# xr_vco_pots.net
KiCad netlist of a schematic drawn in EAGLE
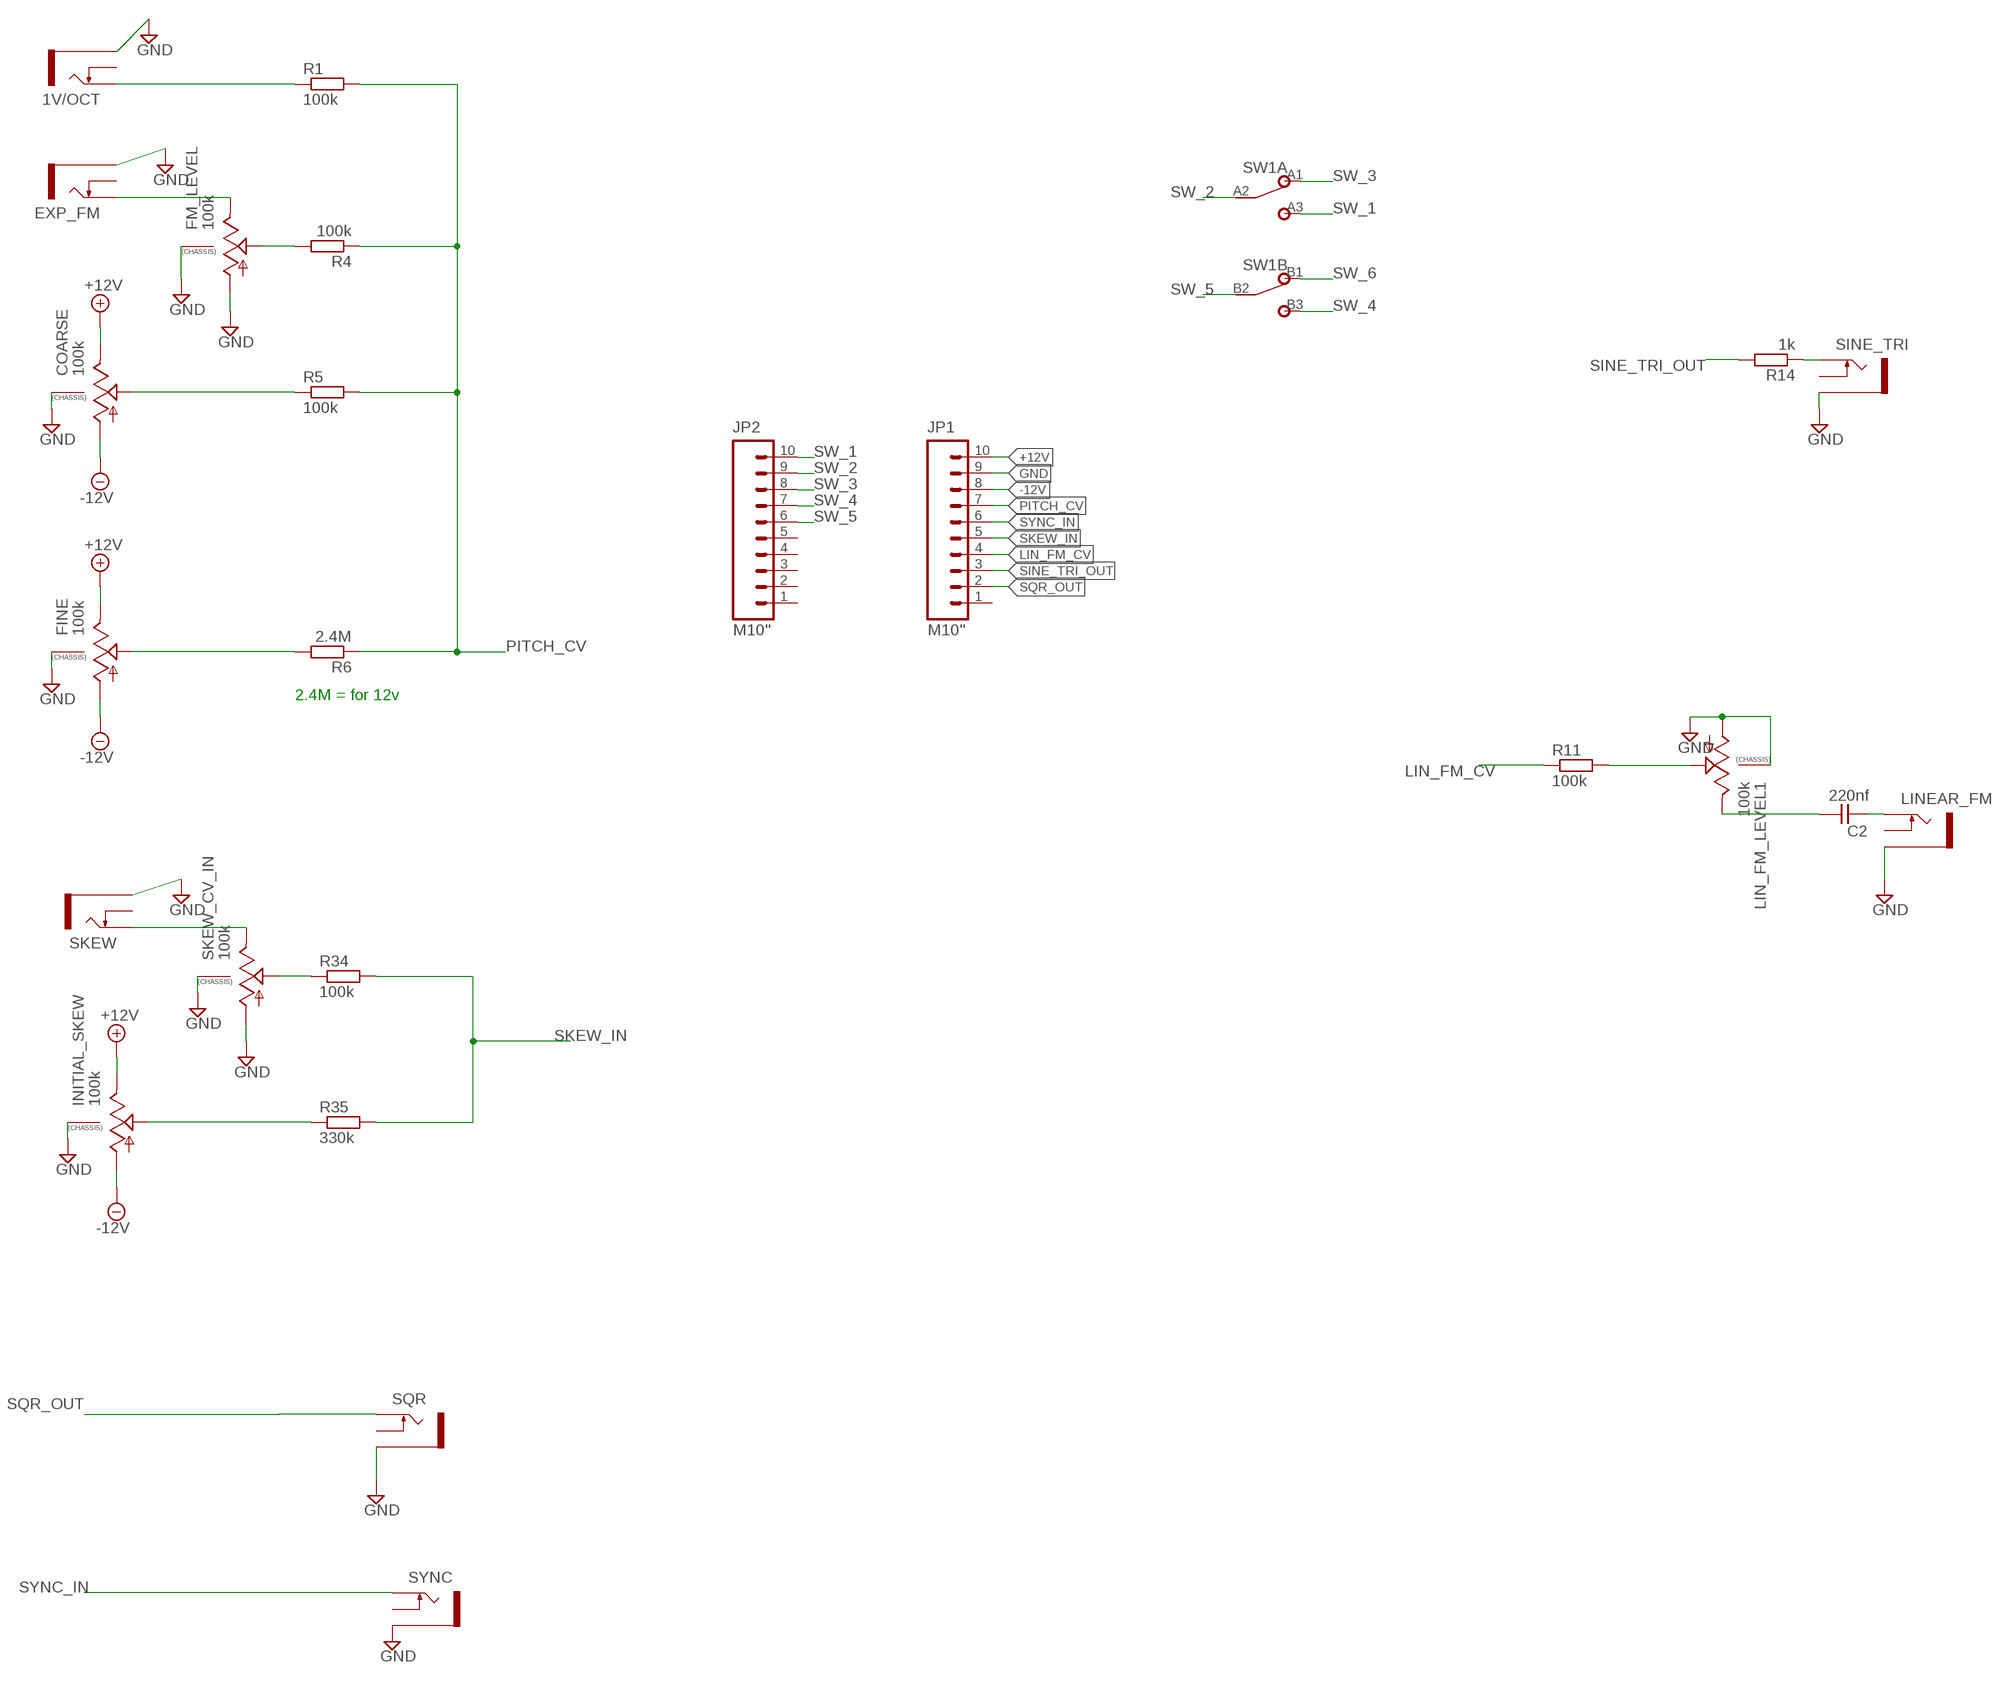
[diagram p0: schematic, sheet 1]

(export (version "E")
  (design (tool "Eeschema 10.0.6"))
  (components
    (comp (ref "1V/OCT")
      (value "THONKICONNNEW")
      (footprint "eagle-import:WQP-PJ301M-12_JACK")
      (libsource (lib "eagle-import") (part "THONKICONNNEW"))
    )
    (comp (ref "C2")
      (value "220nf")
      (footprint "eagle-import:C050-024X044")
      (libsource (lib "eagle-import") (part "C-EU050-024X044"))
    )
    (comp (ref "COARSE")
      (value "100k")
      (footprint "eagle-import:9MM_SNAP-IN_POT")
      (libsource (lib "eagle-import") (part "9MM_SNAP-IN_POT_CHASSIS"))
    )
    (comp (ref "EXP_FM")
      (value "THONKICONNNEW")
      (footprint "eagle-import:WQP-PJ301M-12_JACK")
      (libsource (lib "eagle-import") (part "THONKICONNNEW"))
    )
    (comp (ref "FINE")
      (value "100k")
      (footprint "eagle-import:9MM_SNAP-IN_POT")
      (libsource (lib "eagle-import") (part "9MM_SNAP-IN_POT_CHASSIS"))
    )
    (comp (ref "FM_LEVEL")
      (value "100k")
      (footprint "eagle-import:9MM_SNAP-IN_POT")
      (libsource (lib "eagle-import") (part "9MM_SNAP-IN_POT_CHASSIS"))
    )
    (comp (ref "INITIAL_SKEW")
      (value "100k")
      (footprint "eagle-import:9MM_SNAP-IN_POT")
      (libsource (lib "eagle-import") (part "9MM_SNAP-IN_POT_CHASSIS"))
    )
    (comp (ref "JP1")
      (value "M10\"")
      (footprint "eagle-import:1X10")
      (libsource (lib "eagle-import") (part "M10{dblquote}"))
    )
    (comp (ref "JP2")
      (value "M10\"")
      (footprint "eagle-import:1X10")
      (libsource (lib "eagle-import") (part "M10{dblquote}"))
    )
    (comp (ref "LINEAR_FM")
      (value "THONKICONNNEW")
      (footprint "eagle-import:WQP-PJ301M-12_JACK")
      (libsource (lib "eagle-import") (part "THONKICONNNEW"))
    )
    (comp (ref "LIN_FM_LEVEL1")
      (value "100k")
      (footprint "eagle-import:9MM_SNAP-IN_POT")
      (libsource (lib "eagle-import") (part "9MM_SNAP-IN_POT_CHASSIS"))
    )
    (comp (ref "R1")
      (value "100k")
      (footprint "eagle-import:7MM_RESISTOR")
      (libsource (lib "eagle-import") (part "RESISTOR7MM"))
    )
    (comp (ref "R4")
      (value "100k")
      (footprint "eagle-import:7MM_RESISTOR")
      (libsource (lib "eagle-import") (part "RESISTOR7MM"))
    )
    (comp (ref "R5")
      (value "100k")
      (footprint "eagle-import:7MM_RESISTOR")
      (libsource (lib "eagle-import") (part "RESISTOR7MM"))
    )
    (comp (ref "R6")
      (value "2.4M")
      (footprint "eagle-import:7MM_RESISTOR")
      (libsource (lib "eagle-import") (part "RESISTOR7MM"))
    )
    (comp (ref "R11")
      (value "100k")
      (footprint "eagle-import:7MM_RESISTOR")
      (libsource (lib "eagle-import") (part "RESISTOR7MM"))
    )
    (comp (ref "R14")
      (value "1k")
      (footprint "eagle-import:7MM_RESISTOR")
      (libsource (lib "eagle-import") (part "RESISTOR7MM"))
    )
    (comp (ref "R34")
      (value "100k")
      (footprint "eagle-import:7MM_RESISTOR")
      (libsource (lib "eagle-import") (part "RESISTOR7MM"))
    )
    (comp (ref "R35")
      (value "330k")
      (footprint "eagle-import:7MM_RESISTOR")
      (libsource (lib "eagle-import") (part "RESISTOR7MM"))
    )
    (comp (ref "SINE_TRI")
      (value "THONKICONNNEW")
      (footprint "eagle-import:WQP-PJ301M-12_JACK")
      (libsource (lib "eagle-import") (part "THONKICONNNEW"))
    )
    (comp (ref "SKEW")
      (value "THONKICONNNEW")
      (footprint "eagle-import:WQP-PJ301M-12_JACK")
      (libsource (lib "eagle-import") (part "THONKICONNNEW"))
    )
    (comp (ref "SKEW_CV_IN")
      (value "100k")
      (footprint "eagle-import:9MM_SNAP-IN_POT")
      (libsource (lib "eagle-import") (part "9MM_SNAP-IN_POT_CHASSIS"))
    )
    (comp (ref "SQR")
      (value "THONKICONNNEW")
      (footprint "eagle-import:WQP-PJ301M-12_JACK")
      (libsource (lib "eagle-import") (part "THONKICONNNEW"))
    )
    (comp (ref "SW1")
      (value "DPDT")
      (footprint "eagle-import:DPDT")
      (libsource (lib "eagle-import") (part "DPDT"))
    )
    (comp (ref "SYNC")
      (value "THONKICONNNEW")
      (footprint "eagle-import:WQP-PJ301M-12_JACK")
      (libsource (lib "eagle-import") (part "THONKICONNNEW"))
    )
  )
  (nets
    (net (code "1") (name "+12V") (class "Default")
      (node (ref "COARSE") (pin "3") (pinfunction "E_3") (pintype "passive"))
      (node (ref "FINE") (pin "3") (pinfunction "E_3") (pintype "passive"))
      (node (ref "INITIAL_SKEW") (pin "3") (pinfunction "E_3") (pintype "passive"))
      (node (ref "JP1") (pin "10") (pinfunction "10_10") (pintype "passive"))
    )
    (net (code "2") (name "-12V") (class "Default")
      (node (ref "COARSE") (pin "1") (pinfunction "A_1") (pintype "passive"))
      (node (ref "FINE") (pin "1") (pinfunction "A_1") (pintype "passive"))
      (node (ref "INITIAL_SKEW") (pin "1") (pinfunction "A_1") (pintype "passive"))
      (node (ref "JP1") (pin "8") (pinfunction "8_8") (pintype "passive"))
    )
    (net (code "3") (name "/SW_1") (class "Default")
      (node (ref "JP2") (pin "10") (pinfunction "10_10") (pintype "passive"))
      (node (ref "SW1") (pin "A3") (pinfunction "3_A3") (pintype "passive"))
    )
    (net (code "4") (name "/SW_2") (class "Default")
      (node (ref "JP2") (pin "9") (pinfunction "9_9") (pintype "passive"))
      (node (ref "SW1") (pin "A2") (pinfunction "2_A2") (pintype "passive"))
    )
    (net (code "5") (name "/SW_3") (class "Default")
      (node (ref "JP2") (pin "8") (pinfunction "8_8") (pintype "passive"))
      (node (ref "SW1") (pin "A1") (pinfunction "1_A1") (pintype "passive"))
    )
    (net (code "6") (name "/SW_4") (class "Default")
      (node (ref "JP2") (pin "7") (pinfunction "7_7") (pintype "passive"))
      (node (ref "SW1") (pin "B3") (pinfunction "3_B3") (pintype "passive"))
    )
    (net (code "7") (name "/SW_5") (class "Default")
      (node (ref "JP2") (pin "6") (pinfunction "6_6") (pintype "passive"))
      (node (ref "SW1") (pin "B2") (pinfunction "2_B2") (pintype "passive"))
    )
    (net (code "8") (name "/SW_6") (class "Default")
      (node (ref "SW1") (pin "B1") (pinfunction "1_B1") (pintype "passive"))
    )
    (net (code "9") (name "GND") (class "Default")
      (node (ref "1V/OCT") (pin "P$3_SLEEVE") (pinfunction "SLEEVE_P$3_SLEEVE") (pintype "passive"))
      (node (ref "COARSE") (pin "CHASSIS2") (pinfunction "P$1_CHASSIS2") (pintype "passive"))
      (node (ref "EXP_FM") (pin "P$3_SLEEVE") (pinfunction "SLEEVE_P$3_SLEEVE") (pintype "passive"))
      (node (ref "FINE") (pin "CHASSIS2") (pinfunction "P$1_CHASSIS2") (pintype "passive"))
      (node (ref "FM_LEVEL") (pin "1") (pinfunction "A_1") (pintype "passive"))
      (node (ref "FM_LEVEL") (pin "CHASSIS2") (pinfunction "P$1_CHASSIS2") (pintype "passive"))
      (node (ref "INITIAL_SKEW") (pin "CHASSIS2") (pinfunction "P$1_CHASSIS2") (pintype "passive"))
      (node (ref "JP1") (pin "9") (pinfunction "9_9") (pintype "passive"))
      (node (ref "LINEAR_FM") (pin "P$3_SLEEVE") (pinfunction "SLEEVE_P$3_SLEEVE") (pintype "passive"))
      (node (ref "LIN_FM_LEVEL1") (pin "1") (pinfunction "A_1") (pintype "passive"))
      (node (ref "LIN_FM_LEVEL1") (pin "CHASSIS2") (pinfunction "P$1_CHASSIS2") (pintype "passive"))
      (node (ref "SINE_TRI") (pin "P$3_SLEEVE") (pinfunction "SLEEVE_P$3_SLEEVE") (pintype "passive"))
      (node (ref "SKEW") (pin "P$3_SLEEVE") (pinfunction "SLEEVE_P$3_SLEEVE") (pintype "passive"))
      (node (ref "SKEW_CV_IN") (pin "1") (pinfunction "A_1") (pintype "passive"))
      (node (ref "SKEW_CV_IN") (pin "CHASSIS2") (pinfunction "P$1_CHASSIS2") (pintype "passive"))
      (node (ref "SQR") (pin "P$3_SLEEVE") (pinfunction "SLEEVE_P$3_SLEEVE") (pintype "passive"))
      (node (ref "SYNC") (pin "P$3_SLEEVE") (pinfunction "SLEEVE_P$3_SLEEVE") (pintype "passive"))
    )
    (net (code "10") (name "LIN_FM_CV") (class "Default")
      (node (ref "JP1") (pin "4") (pinfunction "4_4") (pintype "passive"))
      (node (ref "R11") (pin "1") (pinfunction "1_1") (pintype "passive"))
    )
    (net (code "11") (name "Net-(1V/OCT-TIP)") (class "Default")
      (node (ref "1V/OCT") (pin "P$1_TIP") (pinfunction "TIP_P$1_TIP") (pintype "passive"))
      (node (ref "R1") (pin "1") (pinfunction "1_1") (pintype "passive"))
    )
    (net (code "12") (name "Net-(COARSE-S)") (class "Default")
      (node (ref "COARSE") (pin "2") (pinfunction "S_2") (pintype "passive"))
      (node (ref "R5") (pin "1") (pinfunction "1_1") (pintype "passive"))
    )
    (net (code "13") (name "Net-(EXP_FM-TIP)") (class "Default")
      (node (ref "EXP_FM") (pin "P$1_TIP") (pinfunction "TIP_P$1_TIP") (pintype "passive"))
      (node (ref "FM_LEVEL") (pin "3") (pinfunction "E_3") (pintype "passive"))
    )
    (net (code "14") (name "Net-(FINE-S)") (class "Default")
      (node (ref "FINE") (pin "2") (pinfunction "S_2") (pintype "passive"))
      (node (ref "R6") (pin "2") (pinfunction "2_2") (pintype "passive"))
    )
    (net (code "15") (name "Net-(FM_LEVEL-S)") (class "Default")
      (node (ref "FM_LEVEL") (pin "2") (pinfunction "S_2") (pintype "passive"))
      (node (ref "R4") (pin "2") (pinfunction "2_2") (pintype "passive"))
    )
    (net (code "16") (name "Net-(INITIAL_SKEW-S)") (class "Default")
      (node (ref "INITIAL_SKEW") (pin "2") (pinfunction "S_2") (pintype "passive"))
      (node (ref "R35") (pin "1") (pinfunction "1_1") (pintype "passive"))
    )
    (net (code "17") (name "Net-(LINEAR_FM-TIP)") (class "Default")
      (node (ref "C2") (pin "2") (pinfunction "2_2") (pintype "passive"))
      (node (ref "LINEAR_FM") (pin "P$1_TIP") (pinfunction "TIP_P$1_TIP") (pintype "passive"))
    )
    (net (code "18") (name "Net-(LIN_FM_LEVEL1-E)") (class "Default")
      (node (ref "C2") (pin "1") (pinfunction "1_1") (pintype "passive"))
      (node (ref "LIN_FM_LEVEL1") (pin "3") (pinfunction "E_3") (pintype "passive"))
    )
    (net (code "19") (name "Net-(LIN_FM_LEVEL1-S)") (class "Default")
      (node (ref "LIN_FM_LEVEL1") (pin "2") (pinfunction "S_2") (pintype "passive"))
      (node (ref "R11") (pin "2") (pinfunction "2_2") (pintype "passive"))
    )
    (net (code "20") (name "Net-(SINE_TRI-TIP)") (class "Default")
      (node (ref "R14") (pin "1") (pinfunction "1_1") (pintype "passive"))
      (node (ref "SINE_TRI") (pin "P$1_TIP") (pinfunction "TIP_P$1_TIP") (pintype "passive"))
    )
    (net (code "21") (name "Net-(SKEW-TIP)") (class "Default")
      (node (ref "SKEW") (pin "P$1_TIP") (pinfunction "TIP_P$1_TIP") (pintype "passive"))
      (node (ref "SKEW_CV_IN") (pin "3") (pinfunction "E_3") (pintype "passive"))
    )
    (net (code "22") (name "Net-(SKEW_CV_IN-S)") (class "Default")
      (node (ref "R34") (pin "1") (pinfunction "1_1") (pintype "passive"))
      (node (ref "SKEW_CV_IN") (pin "2") (pinfunction "S_2") (pintype "passive"))
    )
    (net (code "23") (name "PITCH_CV") (class "Default")
      (node (ref "JP1") (pin "7") (pinfunction "7_7") (pintype "passive"))
      (node (ref "R1") (pin "2") (pinfunction "2_2") (pintype "passive"))
      (node (ref "R4") (pin "1") (pinfunction "1_1") (pintype "passive"))
      (node (ref "R5") (pin "2") (pinfunction "2_2") (pintype "passive"))
      (node (ref "R6") (pin "1") (pinfunction "1_1") (pintype "passive"))
    )
    (net (code "24") (name "SINE_TRI_OUT") (class "Default")
      (node (ref "JP1") (pin "3") (pinfunction "3_3") (pintype "passive"))
      (node (ref "R14") (pin "2") (pinfunction "2_2") (pintype "passive"))
    )
    (net (code "25") (name "SKEW_IN") (class "Default")
      (node (ref "JP1") (pin "5") (pinfunction "5_5") (pintype "passive"))
      (node (ref "R34") (pin "2") (pinfunction "2_2") (pintype "passive"))
      (node (ref "R35") (pin "2") (pinfunction "2_2") (pintype "passive"))
    )
    (net (code "26") (name "SQR_OUT") (class "Default")
      (node (ref "JP1") (pin "2") (pinfunction "2_2") (pintype "passive"))
      (node (ref "SQR") (pin "P$1_TIP") (pinfunction "TIP_P$1_TIP") (pintype "passive"))
    )
    (net (code "27") (name "SYNC_IN") (class "Default")
      (node (ref "JP1") (pin "6") (pinfunction "6_6") (pintype "passive"))
      (node (ref "SYNC") (pin "P$1_TIP") (pinfunction "TIP_P$1_TIP") (pintype "passive"))
    )
    (net (code "28") (name "unconnected-(1V/OCT-SWITCH-PadP$2_SWITCH)") (class "Default")
      (node (ref "1V/OCT") (pin "P$2_SWITCH") (pinfunction "SWITCH_P$2_SWITCH") (pintype "passive"))
    )
    (net (code "29") (name "unconnected-(EXP_FM-SWITCH-PadP$2_SWITCH)") (class "Default")
      (node (ref "EXP_FM") (pin "P$2_SWITCH") (pinfunction "SWITCH_P$2_SWITCH") (pintype "passive"))
    )
    (net (code "30") (name "unconnected-(JP1-Pad1)") (class "Default")
      (node (ref "JP1") (pin "1") (pinfunction "1_1") (pintype "passive"))
    )
    (net (code "31") (name "unconnected-(JP2-Pad1)") (class "Default")
      (node (ref "JP2") (pin "1") (pinfunction "1_1") (pintype "passive"))
    )
    (net (code "32") (name "unconnected-(JP2-Pad2)") (class "Default")
      (node (ref "JP2") (pin "2") (pinfunction "2_2") (pintype "passive"))
    )
    (net (code "33") (name "unconnected-(JP2-Pad3)") (class "Default")
      (node (ref "JP2") (pin "3") (pinfunction "3_3") (pintype "passive"))
    )
    (net (code "34") (name "unconnected-(JP2-Pad4)") (class "Default")
      (node (ref "JP2") (pin "4") (pinfunction "4_4") (pintype "passive"))
    )
    (net (code "35") (name "unconnected-(JP2-Pad5)") (class "Default")
      (node (ref "JP2") (pin "5") (pinfunction "5_5") (pintype "passive"))
    )
    (net (code "36") (name "unconnected-(LINEAR_FM-SWITCH-PadP$2_SWITCH)") (class "Default")
      (node (ref "LINEAR_FM") (pin "P$2_SWITCH") (pinfunction "SWITCH_P$2_SWITCH") (pintype "passive"))
    )
    (net (code "37") (name "unconnected-(SINE_TRI-SWITCH-PadP$2_SWITCH)") (class "Default")
      (node (ref "SINE_TRI") (pin "P$2_SWITCH") (pinfunction "SWITCH_P$2_SWITCH") (pintype "passive"))
    )
    (net (code "38") (name "unconnected-(SKEW-SWITCH-PadP$2_SWITCH)") (class "Default")
      (node (ref "SKEW") (pin "P$2_SWITCH") (pinfunction "SWITCH_P$2_SWITCH") (pintype "passive"))
    )
    (net (code "39") (name "unconnected-(SQR-SWITCH-PadP$2_SWITCH)") (class "Default")
      (node (ref "SQR") (pin "P$2_SWITCH") (pinfunction "SWITCH_P$2_SWITCH") (pintype "passive"))
    )
    (net (code "40") (name "unconnected-(SYNC-SWITCH-PadP$2_SWITCH)") (class "Default")
      (node (ref "SYNC") (pin "P$2_SWITCH") (pinfunction "SWITCH_P$2_SWITCH") (pintype "passive"))
    )
  )
)
